# synth_backplane_1.net
KiCad netlist of a schematic drawn in EAGLE
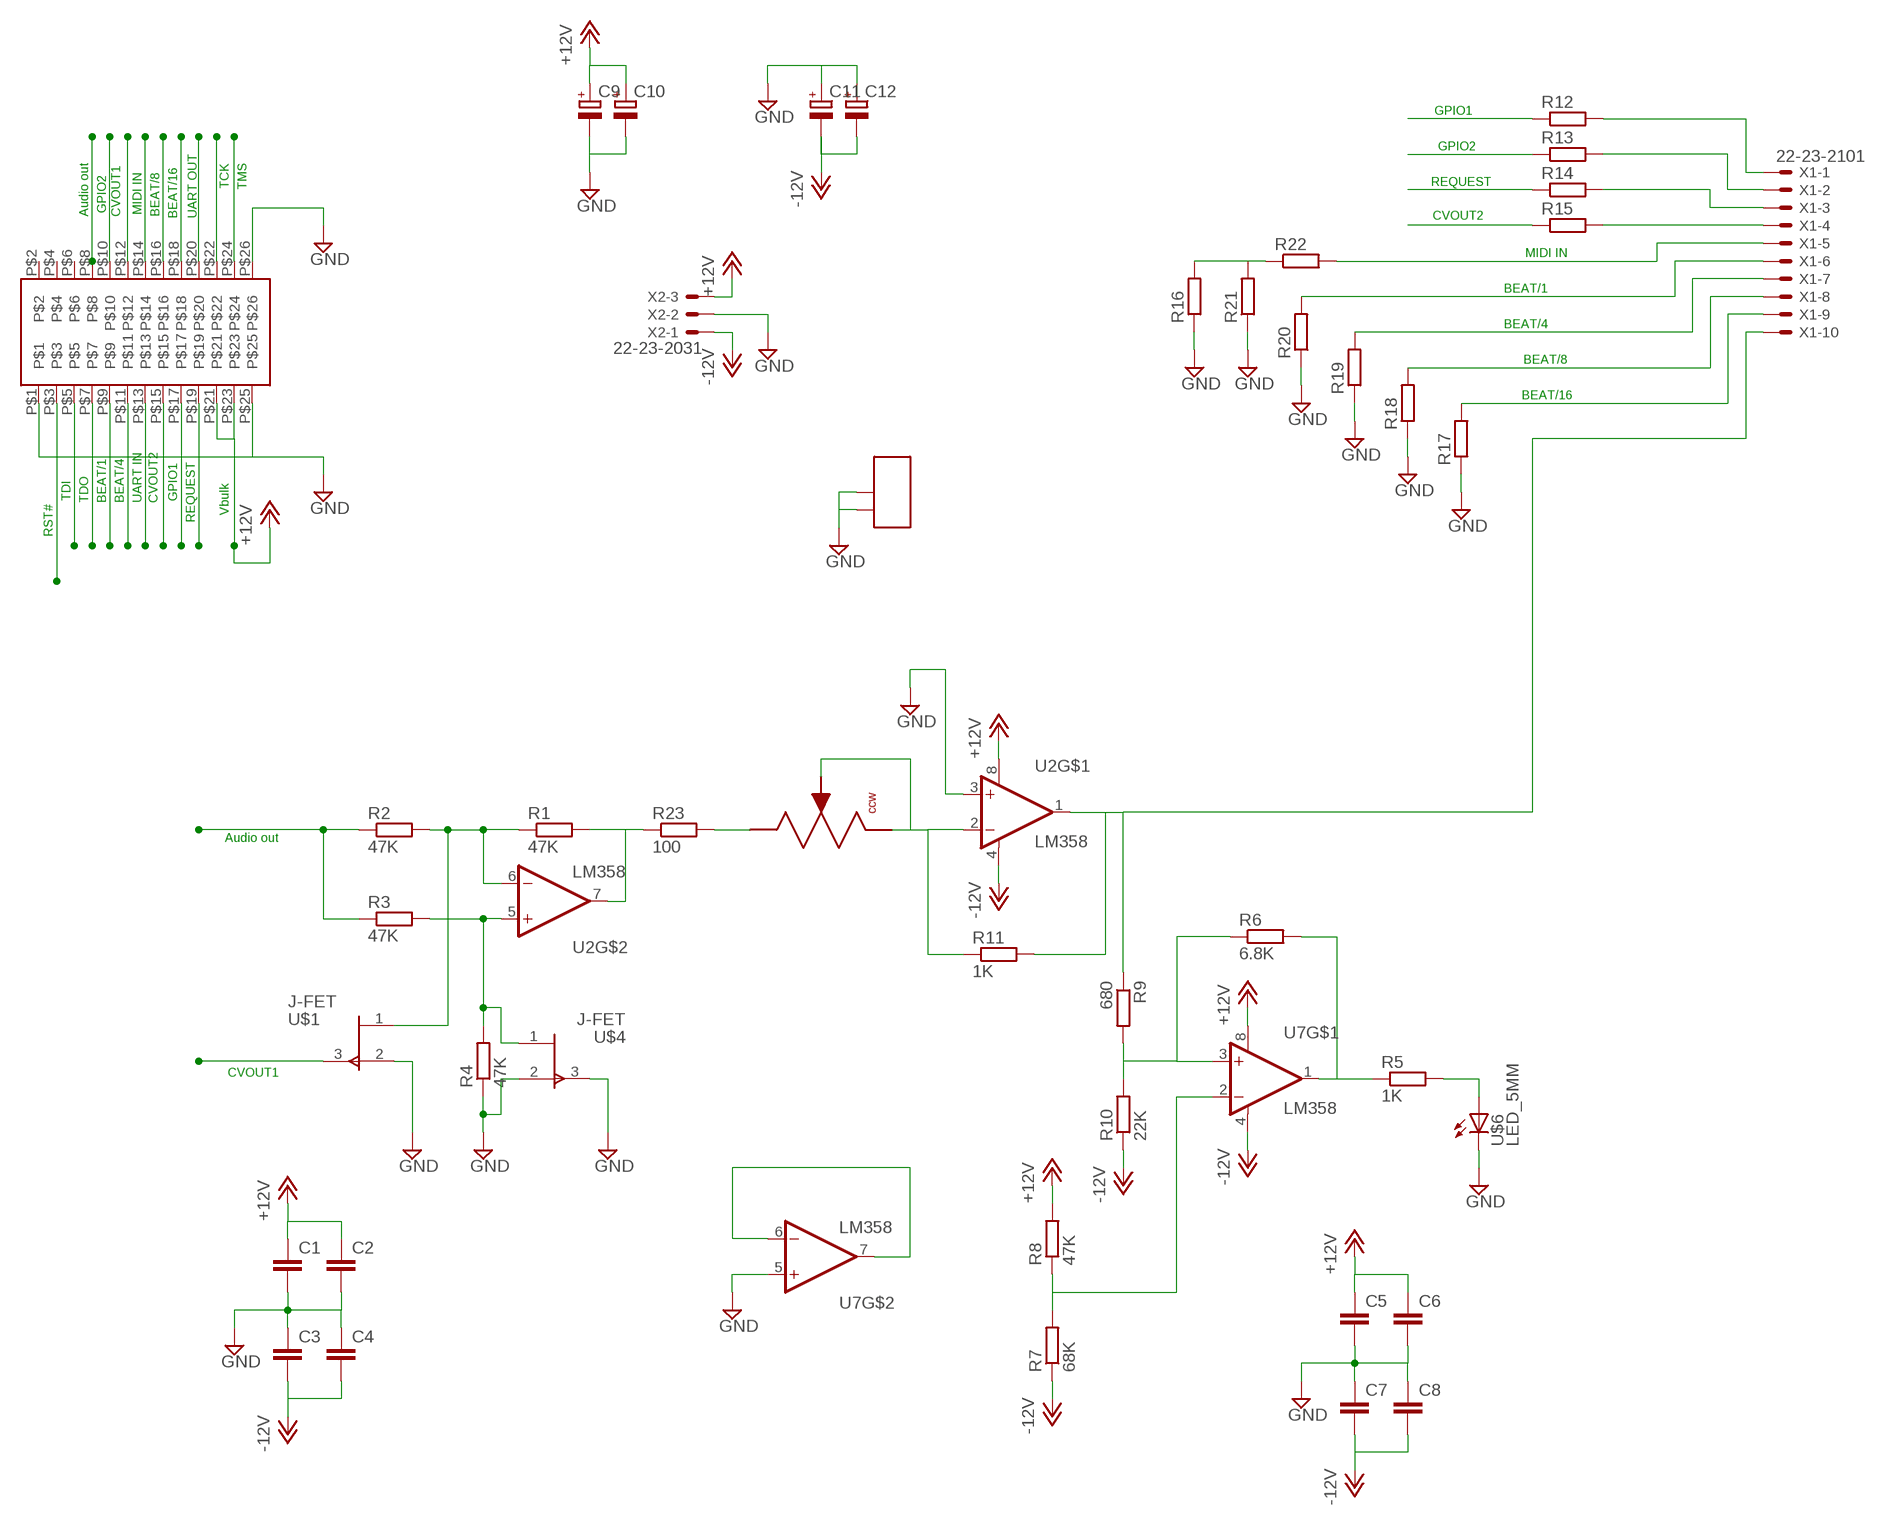
[diagram p0: schematic, sheet 1]

(export (version "E")
  (design (tool "Eeschema 10.0.6"))
  (components
    (comp (ref "C1")
      (value "C-EUC0603K")
      (footprint "eagle-import:C0603K")
      (libsource (lib "eagle-import") (part "C-EUC0603K"))
    )
    (comp (ref "C2")
      (value "C-EUC0603K")
      (footprint "eagle-import:C0603K")
      (libsource (lib "eagle-import") (part "C-EUC0603K"))
    )
    (comp (ref "C3")
      (value "C-EUC0603K")
      (footprint "eagle-import:C0603K")
      (libsource (lib "eagle-import") (part "C-EUC0603K"))
    )
    (comp (ref "C4")
      (value "C-EUC0603K")
      (footprint "eagle-import:C0603K")
      (libsource (lib "eagle-import") (part "C-EUC0603K"))
    )
    (comp (ref "C5")
      (value "C-EUC0603K")
      (footprint "eagle-import:C0603K")
      (libsource (lib "eagle-import") (part "C-EUC0603K"))
    )
    (comp (ref "C6")
      (value "C-EUC0603K")
      (footprint "eagle-import:C0603K")
      (libsource (lib "eagle-import") (part "C-EUC0603K"))
    )
    (comp (ref "C7")
      (value "C-EUC0603K")
      (footprint "eagle-import:C0603K")
      (libsource (lib "eagle-import") (part "C-EUC0603K"))
    )
    (comp (ref "C8")
      (value "C-EUC0603K")
      (footprint "eagle-import:C0603K")
      (libsource (lib "eagle-import") (part "C-EUC0603K"))
    )
    (comp (ref "C9")
      (value "CPOL-EUSMCE")
      (footprint "eagle-import:SMC_E")
      (libsource (lib "eagle-import") (part "CPOL-EUSMCE"))
    )
    (comp (ref "C10")
      (value "CPOL-EUSMCE")
      (footprint "eagle-import:SMC_E")
      (libsource (lib "eagle-import") (part "CPOL-EUSMCE"))
    )
    (comp (ref "C11")
      (value "CPOL-EUSMCE")
      (footprint "eagle-import:SMC_E")
      (libsource (lib "eagle-import") (part "CPOL-EUSMCE"))
    )
    (comp (ref "C12")
      (value "CPOL-EUSMCE")
      (footprint "eagle-import:SMC_E")
      (libsource (lib "eagle-import") (part "CPOL-EUSMCE"))
    )
    (comp (ref "R1")
      (value "47K")
      (footprint "eagle-import:R0603")
      (libsource (lib "eagle-import") (part "R-EU_R0603"))
    )
    (comp (ref "R2")
      (value "47K")
      (footprint "eagle-import:R0603")
      (libsource (lib "eagle-import") (part "R-EU_R0603"))
    )
    (comp (ref "R3")
      (value "47K")
      (footprint "eagle-import:R0603")
      (libsource (lib "eagle-import") (part "R-EU_R0603"))
    )
    (comp (ref "R4")
      (value "47K")
      (footprint "eagle-import:R0603")
      (libsource (lib "eagle-import") (part "R-EU_R0603"))
    )
    (comp (ref "R5")
      (value "1K")
      (footprint "eagle-import:R0603")
      (libsource (lib "eagle-import") (part "R-EU_R0603"))
    )
    (comp (ref "R6")
      (value "6.8K")
      (footprint "eagle-import:R0603")
      (libsource (lib "eagle-import") (part "R-EU_R0603"))
    )
    (comp (ref "R7")
      (value "68K")
      (footprint "eagle-import:R0603")
      (libsource (lib "eagle-import") (part "R-EU_R0603"))
    )
    (comp (ref "R8")
      (value "47K")
      (footprint "eagle-import:R0603")
      (libsource (lib "eagle-import") (part "R-EU_R0603"))
    )
    (comp (ref "R9")
      (value "680")
      (footprint "eagle-import:R0603")
      (libsource (lib "eagle-import") (part "R-EU_R0603"))
    )
    (comp (ref "R10")
      (value "22K")
      (footprint "eagle-import:R0603")
      (libsource (lib "eagle-import") (part "R-EU_R0603"))
    )
    (comp (ref "R11")
      (value "1K")
      (footprint "eagle-import:R0603")
      (libsource (lib "eagle-import") (part "R-EU_R0603"))
    )
    (comp (ref "R12")
      (value "R-EU_R0603")
      (footprint "eagle-import:R0603")
      (libsource (lib "eagle-import") (part "R-EU_R0603"))
    )
    (comp (ref "R13")
      (value "R-EU_R0603")
      (footprint "eagle-import:R0603")
      (libsource (lib "eagle-import") (part "R-EU_R0603"))
    )
    (comp (ref "R14")
      (value "R-EU_R0603")
      (footprint "eagle-import:R0603")
      (libsource (lib "eagle-import") (part "R-EU_R0603"))
    )
    (comp (ref "R15")
      (value "R-EU_R0603")
      (footprint "eagle-import:R0603")
      (libsource (lib "eagle-import") (part "R-EU_R0603"))
    )
    (comp (ref "R16")
      (value "R-EU_R0603")
      (footprint "eagle-import:R0603")
      (libsource (lib "eagle-import") (part "R-EU_R0603"))
    )
    (comp (ref "R17")
      (value "R-EU_R0603")
      (footprint "eagle-import:R0603")
      (libsource (lib "eagle-import") (part "R-EU_R0603"))
    )
    (comp (ref "R18")
      (value "R-EU_R0603")
      (footprint "eagle-import:R0603")
      (libsource (lib "eagle-import") (part "R-EU_R0603"))
    )
    (comp (ref "R19")
      (value "R-EU_R0603")
      (footprint "eagle-import:R0603")
      (libsource (lib "eagle-import") (part "R-EU_R0603"))
    )
    (comp (ref "R20")
      (value "R-EU_R0603")
      (footprint "eagle-import:R0603")
      (libsource (lib "eagle-import") (part "R-EU_R0603"))
    )
    (comp (ref "R21")
      (value "R-EU_R0603")
      (footprint "eagle-import:R0603")
      (libsource (lib "eagle-import") (part "R-EU_R0603"))
    )
    (comp (ref "R22")
      (value "R-EU_R0603")
      (footprint "eagle-import:R0603")
      (libsource (lib "eagle-import") (part "R-EU_R0603"))
    )
    (comp (ref "R23")
      (value "100")
      (footprint "eagle-import:R0603")
      (libsource (lib "eagle-import") (part "R-EU_R0603"))
    )
    (comp (ref "U$1")
      (value "J-FET")
      (footprint "eagle-import:SOT_23")
      (libsource (lib "eagle-import") (part "J-FET"))
    )
    (comp (ref "U$3")
      (value "TE_EDGECON_26_SOCKET")
      (footprint "eagle-import:TE_EDGE_26_SOCKET")
      (libsource (lib "eagle-import") (part "TE_EDGECON_26_SOCKET"))
    )
    (comp (ref "U$4")
      (value "J-FET")
      (footprint "eagle-import:SOT_23")
      (libsource (lib "eagle-import") (part "J-FET"))
    )
    (comp (ref "U$5")
      (value "POT_MODEL_P090")
      (footprint "eagle-import:POT_MODEL_P090")
      (libsource (lib "eagle-import") (part "POT_MODEL_P090"))
    )
    (comp (ref "U$6")
      (value "LED_5MM")
      (footprint "eagle-import:LED5MM")
      (libsource (lib "eagle-import") (part "LED_5MM"))
    )
    (comp (ref "U2")
      (value "LM358")
      (footprint "eagle-import:SO08")
      (libsource (lib "eagle-import") (part "LM358"))
    )
    (comp (ref "U7")
      (value "LM358")
      (footprint "eagle-import:SO08")
      (libsource (lib "eagle-import") (part "LM358"))
    )
    (comp (ref "X1")
      (value "22-23-2101")
      (footprint "eagle-import:22-23-2101")
      (fields (field (name "MF") "MOLEX"))
      (libsource (lib "eagle-import") (part "22-23-2101"))
    )
    (comp (ref "X2")
      (value "22-23-2031")
      (footprint "eagle-import:22-23-2031")
      (fields (field (name "MF") "MOLEX"))
      (libsource (lib "eagle-import") (part "22-23-2031"))
    )
  )
  (nets
    (net (code "1") (name "+12V") (class "Default")
      (node (ref "C1") (pin "1") (pinfunction "1_1") (pintype "passive"))
      (node (ref "C10") (pin "+") (pinfunction "+_+") (pintype "passive"))
      (node (ref "C2") (pin "1") (pinfunction "1_1") (pintype "passive"))
      (node (ref "C5") (pin "1") (pinfunction "1_1") (pintype "passive"))
      (node (ref "C6") (pin "1") (pinfunction "1_1") (pintype "passive"))
      (node (ref "C9") (pin "+") (pinfunction "+_+") (pintype "passive"))
      (node (ref "R8") (pin "2") (pinfunction "2_2") (pintype "passive"))
      (node (ref "U$3") (pin "P$21") (pinfunction "P$21_P$21") (pintype "bidirectional"))
      (node (ref "U$3") (pin "P$23") (pinfunction "P$23_P$23") (pintype "bidirectional"))
      (node (ref "U2") (pin "8") (pinfunction "V+_8") (pintype "power_in"))
      (node (ref "U7") (pin "8") (pinfunction "V+_8") (pintype "power_in"))
      (node (ref "X2") (pin "3") (pinfunction "S_3") (pintype "passive"))
    )
    (net (code "2") (name "-12V") (class "Default")
      (node (ref "C11") (pin "-") (pinfunction "-_-") (pintype "passive"))
      (node (ref "C12") (pin "-") (pinfunction "-_-") (pintype "passive"))
      (node (ref "C3") (pin "2") (pinfunction "2_2") (pintype "passive"))
      (node (ref "C4") (pin "2") (pinfunction "2_2") (pintype "passive"))
      (node (ref "C7") (pin "2") (pinfunction "2_2") (pintype "passive"))
      (node (ref "C8") (pin "2") (pinfunction "2_2") (pintype "passive"))
      (node (ref "R10") (pin "1") (pinfunction "1_1") (pintype "passive"))
      (node (ref "R7") (pin "1") (pinfunction "1_1") (pintype "passive"))
      (node (ref "U2") (pin "4") (pinfunction "V-_4") (pintype "power_in"))
      (node (ref "U7") (pin "4") (pinfunction "V-_4") (pintype "power_in"))
      (node (ref "X2") (pin "1") (pinfunction "S_1") (pintype "passive"))
    )
    (net (code "3") (name "/AUD_OUT") (class "Default")
      (node (ref "R2") (pin "1") (pinfunction "1_1") (pintype "passive"))
      (node (ref "R3") (pin "1") (pinfunction "1_1") (pintype "passive"))
      (node (ref "U$3") (pin "P$8") (pinfunction "P$8_P$8") (pintype "bidirectional"))
    )
    (net (code "4") (name "/BEAT{slash}1") (class "Default")
      (node (ref "R20") (pin "2") (pinfunction "2_2") (pintype "passive"))
      (node (ref "U$3") (pin "P$9") (pinfunction "P$9_P$9") (pintype "bidirectional"))
      (node (ref "X1") (pin "6") (pinfunction "S_6") (pintype "passive"))
    )
    (net (code "5") (name "/BEAT{slash}4") (class "Default")
      (node (ref "R19") (pin "2") (pinfunction "2_2") (pintype "passive"))
      (node (ref "U$3") (pin "P$11") (pinfunction "P$11_P$11") (pintype "bidirectional"))
      (node (ref "X1") (pin "7") (pinfunction "S_7") (pintype "passive"))
    )
    (net (code "6") (name "/BEAT{slash}8") (class "Default")
      (node (ref "R18") (pin "2") (pinfunction "2_2") (pintype "passive"))
      (node (ref "U$3") (pin "P$16") (pinfunction "P$16_P$16") (pintype "bidirectional"))
      (node (ref "X1") (pin "8") (pinfunction "S_8") (pintype "passive"))
    )
    (net (code "7") (name "/BEAT{slash}16") (class "Default")
      (node (ref "R17") (pin "2") (pinfunction "2_2") (pintype "passive"))
      (node (ref "U$3") (pin "P$18") (pinfunction "P$18_P$18") (pintype "bidirectional"))
      (node (ref "X1") (pin "9") (pinfunction "S_9") (pintype "passive"))
    )
    (net (code "8") (name "/CVOUT1") (class "Default")
      (node (ref "U$1") (pin "3") (pinfunction "G_3") (pintype "passive"))
      (node (ref "U$3") (pin "P$12") (pinfunction "P$12_P$12") (pintype "bidirectional"))
    )
    (net (code "9") (name "/CVOUT2") (class "Default")
      (node (ref "R15") (pin "1") (pinfunction "1_1") (pintype "passive"))
      (node (ref "U$3") (pin "P$15") (pinfunction "P$15_P$15") (pintype "bidirectional"))
    )
    (net (code "10") (name "/GPIO1") (class "Default")
      (node (ref "R12") (pin "1") (pinfunction "1_1") (pintype "passive"))
      (node (ref "U$3") (pin "P$17") (pinfunction "P$17_P$17") (pintype "bidirectional"))
    )
    (net (code "11") (name "/GPIO2") (class "Default")
      (node (ref "R13") (pin "1") (pinfunction "1_1") (pintype "passive"))
      (node (ref "U$3") (pin "P$10") (pinfunction "P$10_P$10") (pintype "bidirectional"))
    )
    (net (code "12") (name "/REQUEST") (class "Default")
      (node (ref "R14") (pin "1") (pinfunction "1_1") (pintype "passive"))
      (node (ref "U$3") (pin "P$19") (pinfunction "P$19_P$19") (pintype "bidirectional"))
    )
    (net (code "13") (name "/UCA0RXD") (class "Default")
      (node (ref "R16") (pin "2") (pinfunction "2_2") (pintype "passive"))
      (node (ref "R21") (pin "2") (pinfunction "2_2") (pintype "passive"))
      (node (ref "R22") (pin "1") (pinfunction "1_1") (pintype "passive"))
      (node (ref "U$3") (pin "P$14") (pinfunction "P$14_P$14") (pintype "bidirectional"))
    )
    (net (code "14") (name "GND") (class "Default")
      (node (ref "C1") (pin "2") (pinfunction "2_2") (pintype "passive"))
      (node (ref "C10") (pin "-") (pinfunction "-_-") (pintype "passive"))
      (node (ref "C11") (pin "+") (pinfunction "+_+") (pintype "passive"))
      (node (ref "C12") (pin "+") (pinfunction "+_+") (pintype "passive"))
      (node (ref "C2") (pin "2") (pinfunction "2_2") (pintype "passive"))
      (node (ref "C3") (pin "1") (pinfunction "1_1") (pintype "passive"))
      (node (ref "C4") (pin "1") (pinfunction "1_1") (pintype "passive"))
      (node (ref "C5") (pin "2") (pinfunction "2_2") (pintype "passive"))
      (node (ref "C6") (pin "2") (pinfunction "2_2") (pintype "passive"))
      (node (ref "C7") (pin "1") (pinfunction "1_1") (pintype "passive"))
      (node (ref "C8") (pin "1") (pinfunction "1_1") (pintype "passive"))
      (node (ref "C9") (pin "-") (pinfunction "-_-") (pintype "passive"))
      (node (ref "R16") (pin "1") (pinfunction "1_1") (pintype "passive"))
      (node (ref "R17") (pin "1") (pinfunction "1_1") (pintype "passive"))
      (node (ref "R18") (pin "1") (pinfunction "1_1") (pintype "passive"))
      (node (ref "R19") (pin "1") (pinfunction "1_1") (pintype "passive"))
      (node (ref "R20") (pin "1") (pinfunction "1_1") (pintype "passive"))
      (node (ref "R21") (pin "1") (pinfunction "1_1") (pintype "passive"))
      (node (ref "R4") (pin "1") (pinfunction "1_1") (pintype "passive"))
      (node (ref "U$1") (pin "2") (pinfunction "S_2") (pintype "passive"))
      (node (ref "U$3") (pin "P$1") (pinfunction "P$1_P$1") (pintype "bidirectional"))
      (node (ref "U$3") (pin "P$25") (pinfunction "P$25_P$25") (pintype "bidirectional"))
      (node (ref "U$3") (pin "P$26") (pinfunction "P$26_P$26") (pintype "bidirectional"))
      (node (ref "U$4") (pin "2") (pinfunction "S_2") (pintype "passive"))
      (node (ref "U$4") (pin "3") (pinfunction "G_3") (pintype "passive"))
      (node (ref "U$5") (pin "P$4") (pinfunction "P$1_P$4") (pintype "bidirectional"))
      (node (ref "U$5") (pin "P$5") (pinfunction "P$2_P$5") (pintype "bidirectional"))
      (node (ref "U$6") (pin "K") (pinfunction "C_K") (pintype "passive"))
      (node (ref "U2") (pin "3") (pinfunction "+IN_3") (pintype "input"))
      (node (ref "U7") (pin "5") (pinfunction "+IN_5") (pintype "input"))
      (node (ref "X2") (pin "2") (pinfunction "S_2") (pintype "passive"))
    )
    (net (code "15") (name "Net-(R5-Pad2)") (class "Default")
      (node (ref "R5") (pin "2") (pinfunction "2_2") (pintype "passive"))
      (node (ref "U$6") (pin "A") (pinfunction "A_A") (pintype "passive"))
    )
    (net (code "16") (name "Net-(U$1-D)") (class "Default")
      (node (ref "R1") (pin "1") (pinfunction "1_1") (pintype "passive"))
      (node (ref "R2") (pin "2") (pinfunction "2_2") (pintype "passive"))
      (node (ref "U$1") (pin "1") (pinfunction "D_1") (pintype "passive"))
      (node (ref "U2") (pin "6") (pinfunction "-IN_6") (pintype "input"))
    )
    (net (code "17") (name "Net-(U$4-D)") (class "Default")
      (node (ref "R3") (pin "2") (pinfunction "2_2") (pintype "passive"))
      (node (ref "R4") (pin "2") (pinfunction "2_2") (pintype "passive"))
      (node (ref "U$4") (pin "1") (pinfunction "D_1") (pintype "passive"))
      (node (ref "U2") (pin "5") (pinfunction "+IN_5") (pintype "input"))
    )
    (net (code "18") (name "Net-(U$5A-CCW)") (class "Default")
      (node (ref "R11") (pin "1") (pinfunction "1_1") (pintype "passive"))
      (node (ref "U$5") (pin "P$2") (pinfunction "RVAR_P$2") (pintype "bidirectional"))
      (node (ref "U$5") (pin "P$3") (pinfunction "CCW_P$3") (pintype "bidirectional"))
      (node (ref "U2") (pin "2") (pinfunction "-IN_2") (pintype "input"))
    )
    (net (code "19") (name "Net-(U$5A-R2)") (class "Default")
      (node (ref "R23") (pin "2") (pinfunction "2_2") (pintype "passive"))
      (node (ref "U$5") (pin "P$1") (pinfunction "R2_P$1") (pintype "bidirectional"))
    )
    (net (code "20") (name "Net-(U2A-OUT)") (class "Default")
      (node (ref "R11") (pin "2") (pinfunction "2_2") (pintype "passive"))
      (node (ref "R9") (pin "1") (pinfunction "1_1") (pintype "passive"))
      (node (ref "U2") (pin "1") (pinfunction "OUT_1") (pintype "output"))
      (node (ref "X1") (pin "10") (pinfunction "S_10") (pintype "passive"))
    )
    (net (code "21") (name "Net-(U2B-OUT)") (class "Default")
      (node (ref "R1") (pin "2") (pinfunction "2_2") (pintype "passive"))
      (node (ref "R23") (pin "1") (pinfunction "1_1") (pintype "passive"))
      (node (ref "U2") (pin "7") (pinfunction "OUT_7") (pintype "output"))
    )
    (net (code "22") (name "Net-(U7A-+IN)") (class "Default")
      (node (ref "R10") (pin "2") (pinfunction "2_2") (pintype "passive"))
      (node (ref "R6") (pin "1") (pinfunction "1_1") (pintype "passive"))
      (node (ref "R9") (pin "2") (pinfunction "2_2") (pintype "passive"))
      (node (ref "U7") (pin "3") (pinfunction "+IN_3") (pintype "input"))
    )
    (net (code "23") (name "Net-(U7A--IN)") (class "Default")
      (node (ref "R7") (pin "2") (pinfunction "2_2") (pintype "passive"))
      (node (ref "R8") (pin "1") (pinfunction "1_1") (pintype "passive"))
      (node (ref "U7") (pin "2") (pinfunction "-IN_2") (pintype "input"))
    )
    (net (code "24") (name "Net-(U7A-OUT)") (class "Default")
      (node (ref "R5") (pin "1") (pinfunction "1_1") (pintype "passive"))
      (node (ref "R6") (pin "2") (pinfunction "2_2") (pintype "passive"))
      (node (ref "U7") (pin "1") (pinfunction "OUT_1") (pintype "output"))
    )
    (net (code "25") (name "Net-(U7B--IN)") (class "Default")
      (node (ref "U7") (pin "6") (pinfunction "-IN_6") (pintype "input"))
      (node (ref "U7") (pin "7") (pinfunction "OUT_7") (pintype "output"))
    )
    (net (code "26") (name "Net-(X1A-S)") (class "Default")
      (node (ref "R12") (pin "2") (pinfunction "2_2") (pintype "passive"))
      (node (ref "X1") (pin "1") (pinfunction "S_1") (pintype "passive"))
    )
    (net (code "27") (name "Net-(X1C-S)") (class "Default")
      (node (ref "R13") (pin "2") (pinfunction "2_2") (pintype "passive"))
      (node (ref "X1") (pin "2") (pinfunction "S_2") (pintype "passive"))
    )
    (net (code "28") (name "Net-(X1D-S)") (class "Default")
      (node (ref "R14") (pin "2") (pinfunction "2_2") (pintype "passive"))
      (node (ref "X1") (pin "3") (pinfunction "S_3") (pintype "passive"))
    )
    (net (code "29") (name "Net-(X1E-S)") (class "Default")
      (node (ref "R15") (pin "2") (pinfunction "2_2") (pintype "passive"))
      (node (ref "X1") (pin "4") (pinfunction "S_4") (pintype "passive"))
    )
    (net (code "30") (name "Net-(X1F-S)") (class "Default")
      (node (ref "R22") (pin "2") (pinfunction "2_2") (pintype "passive"))
      (node (ref "X1") (pin "5") (pinfunction "S_5") (pintype "passive"))
    )
    (net (code "31") (name "unconnected-(U$3-PadP$2)") (class "Default")
      (node (ref "U$3") (pin "P$2") (pinfunction "P$2_P$2") (pintype "bidirectional"))
    )
    (net (code "32") (name "unconnected-(U$3-PadP$3)") (class "Default")
      (node (ref "U$3") (pin "P$3") (pinfunction "P$3_P$3") (pintype "bidirectional"))
    )
    (net (code "33") (name "unconnected-(U$3-PadP$4)") (class "Default")
      (node (ref "U$3") (pin "P$4") (pinfunction "P$4_P$4") (pintype "bidirectional"))
    )
    (net (code "34") (name "unconnected-(U$3-PadP$5)") (class "Default")
      (node (ref "U$3") (pin "P$5") (pinfunction "P$5_P$5") (pintype "bidirectional"))
    )
    (net (code "35") (name "unconnected-(U$3-PadP$6)") (class "Default")
      (node (ref "U$3") (pin "P$6") (pinfunction "P$6_P$6") (pintype "bidirectional"))
    )
    (net (code "36") (name "unconnected-(U$3-PadP$7)") (class "Default")
      (node (ref "U$3") (pin "P$7") (pinfunction "P$7_P$7") (pintype "bidirectional"))
    )
    (net (code "37") (name "unconnected-(U$3-PadP$13)") (class "Default")
      (node (ref "U$3") (pin "P$13") (pinfunction "P$13_P$13") (pintype "bidirectional"))
    )
    (net (code "38") (name "unconnected-(U$3-PadP$20)") (class "Default")
      (node (ref "U$3") (pin "P$20") (pinfunction "P$20_P$20") (pintype "bidirectional"))
    )
    (net (code "39") (name "unconnected-(U$3-PadP$22)") (class "Default")
      (node (ref "U$3") (pin "P$22") (pinfunction "P$22_P$22") (pintype "bidirectional"))
    )
    (net (code "40") (name "unconnected-(U$3-PadP$24)") (class "Default")
      (node (ref "U$3") (pin "P$24") (pinfunction "P$24_P$24") (pintype "bidirectional"))
    )
  )
)
